# Power_RPI_conn.net
KiCad netlist of a schematic drawn in Altium Designer
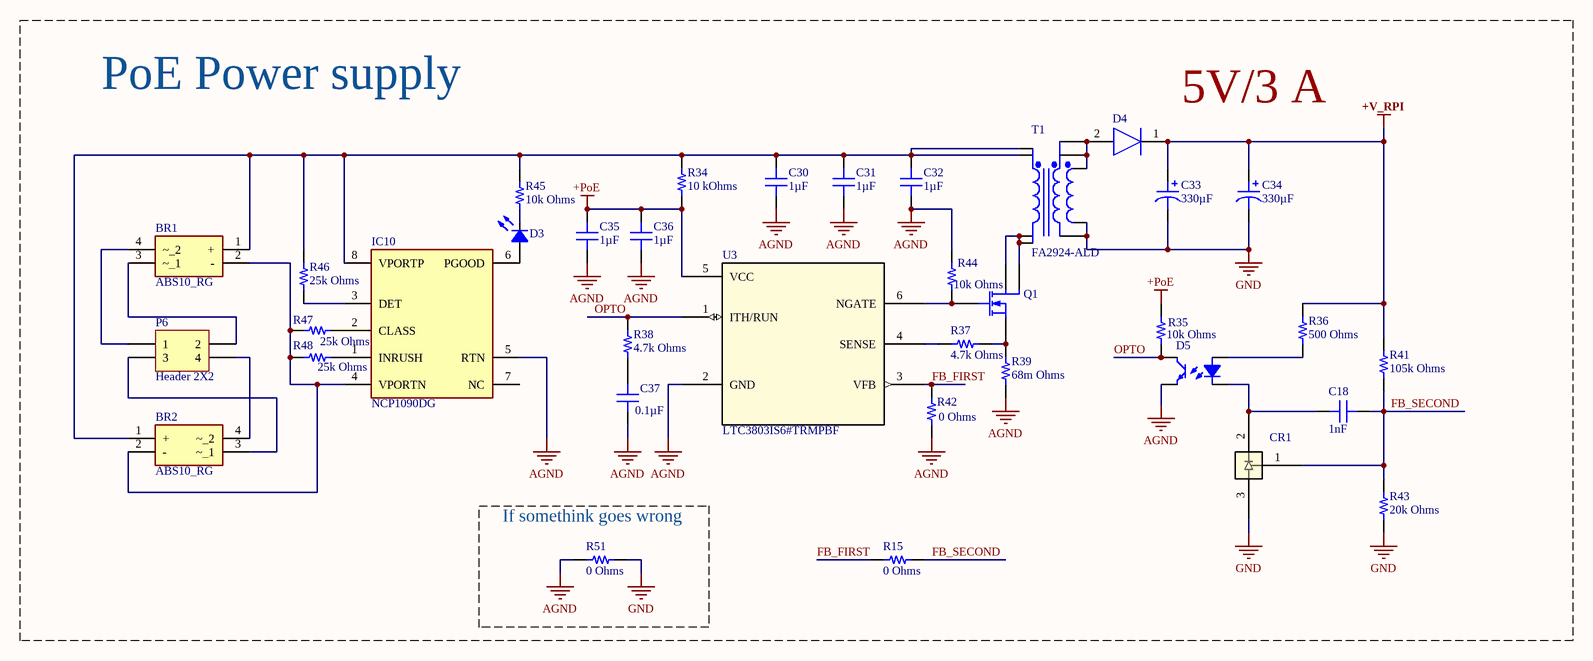
[diagram p0: Power+RPI_conn.SchDoc]

(export (version "E")
  (design (tool "Eeschema 10.0.6"))
  (components
    (comp (ref "BR1")
      (value "ABS10_RG")
      (footprint "SamacSys:SOP400P645X160-4N")
      (description "Bridge Rectifier")
      (fields (field (name "MANUFACTURER_PART_NUMBER") "ABS10 RG"))
      (libsource (lib "*") (part "ABS10_RG"))
    )
    (comp (ref "BR2")
      (value "ABS10_RG")
      (footprint "SamacSys:SOP400P645X160-4N")
      (description "Bridge Rectifier")
      (fields (field (name "MANUFACTURER_PART_NUMBER") "ABS10 RG"))
      (libsource (lib "") (part "ABS10_RG_1"))
    )
    (comp (ref "C18")
      (value "1nF")
      (footprint "CAP 0603_1608")
      (description "CAP CER 0.1UF 10V X7R 0603")
      (fields (field (name "PART NUMBER") "100X14W104MV4T"))
      (libsource (lib "Celestial Altium Library - altium_library") (part "Capacitor"))
    )
    (comp (ref "C30")
      (value "1µF")
      (footprint "CAP 1206_3216 - 1.8MM")
      (description "CAP CER 1UF 100V X7R 1206")
      (fields (field (name "PART NUMBER") "C1206C105M1RACTU") (field (name "MANUFACTURER") "KEMET"))
      (libsource (lib "Celestial Altium Library - altium_library") (part "Capacitor"))
    )
    (comp (ref "C31")
      (value "1µF")
      (footprint "CAP 1206_3216 - 1.8MM")
      (description "CAP CER 1UF 100V X7R 1206")
      (fields (field (name "PART NUMBER") "C1206C105M1RACTU") (field (name "MANUFACTURER") "KEMET"))
      (libsource (lib "Celestial Altium Library - altium_library") (part "Capacitor"))
    )
    (comp (ref "C32")
      (value "1µF")
      (footprint "CAP 1206_3216 - 1.8MM")
      (description "CAP CER 1UF 100V X7R 1206")
      (fields (field (name "PART NUMBER") "C1206C105M1RACTU") (field (name "MANUFACTURER") "KEMET"))
      (libsource (lib "Celestial Altium Library - altium_library") (part "Capacitor"))
    )
    (comp (ref "C33")
      (value "330µF")
      (footprint "CAP POL 2917_7343")
      (description "CAP TANT 330UF 20% 10V 2917")
      (fields (field (name "PART NUMBER") "TPSE337M010R0060") (field (name "MANUFACTURER") "AVX Corporation"))
      (libsource (lib "Celestial Altium Library - altium_library") (part "Polarised Capacitor"))
    )
    (comp (ref "C34")
      (value "330µF")
      (footprint "CAP POL 2917_7343")
      (description "CAP TANT 330UF 20% 10V 2917")
      (fields (field (name "PART NUMBER") "TPSE337M010R0060") (field (name "MANUFACTURER") "AVX Corporation"))
      (libsource (lib "Celestial Altium Library - altium_library") (part "Polarised Capacitor"))
    )
    (comp (ref "C35")
      (value "1µF")
      (footprint "CAP 1206_3216 - 1.8MM")
      (description "CAP CER 1UF 100V X7R 1206")
      (fields (field (name "PART NUMBER") "C1206C105M1RACTU") (field (name "MANUFACTURER") "KEMET"))
      (libsource (lib "Celestial Altium Library - altium_library") (part "Capacitor"))
    )
    (comp (ref "C36")
      (value "1µF")
      (footprint "CAP 1206_3216 - 1.8MM")
      (description "CAP CER 1UF 100V X7R 1206")
      (fields (field (name "PART NUMBER") "C1206C105M1RACTU") (field (name "MANUFACTURER") "KEMET"))
      (libsource (lib "Celestial Altium Library - altium_library") (part "Capacitor"))
    )
    (comp (ref "C37")
      (value "0.1µF")
      (footprint "CAP 0603_1608")
      (description "CAP CER 0.1UF 10V X7R 0603")
      (fields (field (name "PART NUMBER") "100X14W104MV4T"))
      (libsource (lib "Celestial Altium Library - altium_library") (part "Capacitor"))
    )
    (comp (ref "CR1")
      (value "TLV431BFTA")
      (footprint "SOT23_DIO")
      (description "No Description Available")
      (fields (field (name "COPYRIGHT") "Copyright (C) 2018 Accelerated Designs. All rights reserved"))
      (libsource (lib "tlv431") (part "TLV431BFTA"))
    )
    (comp (ref "D3")
      (value "~")
      (footprint "LED 0603_1608 RED")
      (description "LED RED 0603 SMD")
      (fields (field (name "PART NUMBER") "5973005507F"))
      (libsource (lib "Celestial Altium Library - altium_library") (part "LED"))
    )
    (comp (ref "D4")
      (value "SK56B_R4")
      (footprint "SamacSys:DIONM5236X261N")
      (description "Diode")
      (fields
        (field (name "MANUFACTURER_PART_NUMBER") "SK56B R4")
        (field (name "MOUSER PART NUMBER") "821-SK56BR4")
      )
      (libsource (lib "*") (part "SK56B_R4"))
    )
    (comp (ref "D5")
      (value "LTV-817S-TA1")
      (footprint "LITEON LTV-817")
      (description "OPTOISOLATR 5KV TRANSISTOR 4-SMD")
      (fields (field (name "MANUFACTURER") "Lite-On Inc."))
      (libsource (lib "Celestial Altium Library - altium_library") (part "Optoisolator"))
    )
    (comp (ref "IC10")
      (value "NCP1090DG")
      (footprint "SamacSys:SOIC127P600X175-8N")
      (description "Integrated Circuit")
      (fields (field (name "MOUSER PART NUMBER") "863-NCP1090DG"))
      (libsource (lib "SamacSys") (part "NCP1090DG"))
    )
    (comp (ref "P6")
      (value "Header 2X2")
      (footprint "HDR2X2")
      (description "Header, 2-Pin, Dual row")
      (fields (field (name "PUBLISHER") "Altium Limited"))
      (libsource (lib "Miscellaneous Connectors") (part "Header 2X2"))
    )
    (comp (ref "Q1")
      (value "IRFL4315TRPBF")
      (footprint "SOT230P700X180-4N")
      (description "MOSFET (N-Channel)")
      (fields (field (name "MOUSER PART NUMBER") "942-IRFL4315TRPBF"))
      (libsource (lib "SamacSys") (part "IRFL4315TRPBF"))
    )
    (comp (ref "R15")
      (value "0 Ohms")
      (footprint "RES 2512_6432")
      (description "RES 0 OHM JUMPER 1W 2512")
      (fields
        (field (name "PART NUMBER") "RMCF2512ZT0R00")
        (field (name "MANUFACTURER") "Stackpole Electronics Inc")
      )
      (libsource (lib "Celestial Altium Library - altium_library") (part "Resistor"))
    )
    (comp (ref "R34")
      (value "10 kOhms")
      (footprint "RES 1206_3216")
      (description "RES SMD 33K OHM 0.1% 1/4W 1206")
      (fields (field (name "PART NUMBER") "RT1206BRD0733KL") (field (name "MANUFACTURER") "Yageo"))
      (libsource (lib "Celestial Altium Library - altium_library") (part "Resistor"))
    )
    (comp (ref "R35")
      (value "10k Ohms")
      (footprint "RES 0603_1608")
      (description "RES 100 OHM 0.1% 1/16W 0603")
      (fields (field (name "PART NUMBER") "RNCS0603BKE100R"))
      (libsource (lib "Celestial Altium Library - altium_library") (part "Resistor"))
    )
    (comp (ref "R36")
      (value "500 Ohms")
      (footprint "RES 0603_1608")
      (description "RES 100 OHM 0.1% 1/16W 0603")
      (fields (field (name "PART NUMBER") "RNCS0603BKE100R"))
      (libsource (lib "Celestial Altium Library - altium_library") (part "Resistor"))
    )
    (comp (ref "R37")
      (value "4.7k Ohms")
      (footprint "RES 0603_1608")
      (description "RES 100 OHM 0.1% 1/16W 0603")
      (fields (field (name "PART NUMBER") "RNCS0603BKE100R"))
      (libsource (lib "Celestial Altium Library - altium_library") (part "Resistor"))
    )
    (comp (ref "R38")
      (value "4.7k Ohms")
      (footprint "RES 0603_1608")
      (description "RES 100 OHM 0.1% 1/16W 0603")
      (fields (field (name "PART NUMBER") "RNCS0603BKE100R"))
      (libsource (lib "Celestial Altium Library - altium_library") (part "Resistor"))
    )
    (comp (ref "R39")
      (value "68m Ohms")
      (footprint "RES 1206_3216")
      (description "1206 SIZE, 0.25W, 350 OHM, 0.01%")
      (fields (field (name "PART NUMBER") "URG3216L-3500-L-T05") (field (name "MANUFACTURER") "Susumu"))
      (libsource (lib "Celestial Altium Library - altium_library") (part "Resistor"))
    )
    (comp (ref "R41")
      (value "105k Ohms")
      (footprint "RES 0603_1608")
      (description "RES 100 OHM 0.1% 1/16W 0603")
      (fields (field (name "PART NUMBER") "RNCS0603BKE100R"))
      (libsource (lib "Celestial Altium Library - altium_library") (part "Resistor"))
    )
    (comp (ref "R42")
      (value "0 Ohms")
      (footprint "RES 0603_1608")
      (description "RES 100 OHM 0.1% 1/16W 0603")
      (fields (field (name "PART NUMBER") "RNCS0603BKE100R"))
      (libsource (lib "Celestial Altium Library - altium_library") (part "Resistor"))
    )
    (comp (ref "R43")
      (value "20k Ohms")
      (footprint "RES 0603_1608")
      (description "RES 100 OHM 0.1% 1/16W 0603")
      (fields (field (name "PART NUMBER") "RNCS0603BKE100R"))
      (libsource (lib "Celestial Altium Library - altium_library") (part "Resistor"))
    )
    (comp (ref "R44")
      (value "10k Ohms")
      (footprint "RES 0603_1608")
      (description "RES 100 OHM 0.1% 1/16W 0603")
      (fields (field (name "PART NUMBER") "RNCS0603BKE100R"))
      (libsource (lib "Celestial Altium Library - altium_library") (part "Resistor"))
    )
    (comp (ref "R45")
      (value "10k Ohms")
      (footprint "RES 0603_1608")
      (description "RES 100 OHM 0.1% 1/16W 0603")
      (fields (field (name "PART NUMBER") "RNCS0603BKE100R"))
      (libsource (lib "Celestial Altium Library - altium_library") (part "Resistor"))
    )
    (comp (ref "R46")
      (value "25k Ohms")
      (footprint "RES 0603_1608")
      (description "RES 100 OHM 0.1% 1/16W 0603")
      (fields (field (name "PART NUMBER") "RNCS0603BKE100R"))
      (libsource (lib "Celestial Altium Library - altium_library") (part "Resistor"))
    )
    (comp (ref "R47")
      (value "25k Ohms")
      (footprint "RES 0603_1608")
      (description "RES 100 OHM 0.1% 1/16W 0603")
      (fields (field (name "PART NUMBER") "RNCS0603BKE100R"))
      (libsource (lib "Celestial Altium Library - altium_library") (part "Resistor"))
    )
    (comp (ref "R48")
      (value "25k Ohms")
      (footprint "RES 0603_1608")
      (description "RES 100 OHM 0.1% 1/16W 0603")
      (fields (field (name "PART NUMBER") "RNCS0603BKE100R"))
      (libsource (lib "Celestial Altium Library - altium_library") (part "Resistor"))
    )
    (comp (ref "R51")
      (value "0 Ohms")
      (footprint "RES 2512_6432")
      (description "RES 0 OHM JUMPER 1W 2512")
      (fields
        (field (name "PART NUMBER") "RMCF2512ZT0R00")
        (field (name "MANUFACTURER") "Stackpole Electronics Inc")
      )
      (libsource (lib "Celestial Altium Library - altium_library") (part "Resistor"))
    )
    (comp (ref "T1")
      (value "FA2924-ALD")
      (footprint "SamacSys2:FA2924ALD")
      (description "Transformer")
      (fields (field (name "MOUSER PART NUMBER") "994-FA2924-ALD"))
      (libsource (lib "RPI_POE_ADC_SHIELD") (part "FA2924-ALD"))
    )
    (comp (ref "U3")
      (value "LTC3803IS6#TRMPBF")
      (footprint "SamacSys:SOT95P280X100-6N")
      (description "No Description Available")
      (fields
        (field (name "MANUFACTURER_PART_NUMBER") "LTC3803IS6-5#TRMPBF")
        (field (name "COPYRIGHT") "Copyright (C) 2018 Accelerated Designs. All rights reserved")
      )
      (libsource (lib "LTC3803") (part "LTC3803IS6-5#TRMPBF"))
    )
  )
  (nets
    (net (code "1") (name "+PoE") (class "Default")
      (node (ref "C35") (pin "2") (pinfunction "2_2") (pintype "passive"))
      (node (ref "C36") (pin "2") (pinfunction "2_2") (pintype "passive"))
      (node (ref "R34") (pin "1") (pinfunction "1_1") (pintype "passive"))
      (node (ref "R35") (pin "2") (pinfunction "2_2") (pintype "passive"))
      (node (ref "U3") (pin "5") (pinfunction "VCC_5") (pintype "power_in"))
    )
    (net (code "2") (name "+V_RPI") (class "Default")
      (node (ref "C33") (pin "1") (pinfunction "1_1") (pintype "passive"))
      (node (ref "C34") (pin "1") (pinfunction "1_1") (pintype "passive"))
      (node (ref "D4") (pin "1") (pinfunction "K_1") (pintype "passive"))
      (node (ref "R36") (pin "2") (pinfunction "2_2") (pintype "passive"))
      (node (ref "R41") (pin "1") (pinfunction "1_1") (pintype "passive"))
    )
    (net (code "3") (name "/FB_FIRST") (class "Default")
      (node (ref "R15") (pin "1") (pinfunction "1_1") (pintype "passive"))
      (node (ref "R42") (pin "1") (pinfunction "1_1") (pintype "passive"))
      (node (ref "U3") (pin "3") (pinfunction "VFB_3") (pintype "output"))
    )
    (net (code "4") (name "/FB_SECOND") (class "Default")
      (node (ref "C18") (pin "1") (pinfunction "1_1") (pintype "passive"))
      (node (ref "CR1") (pin "1") (pinfunction "1_1") (pintype "passive"))
      (node (ref "R15") (pin "2") (pinfunction "2_2") (pintype "passive"))
      (node (ref "R41") (pin "2") (pinfunction "2_2") (pintype "passive"))
      (node (ref "R43") (pin "1") (pinfunction "1_1") (pintype "passive"))
    )
    (net (code "5") (name "/OPTO") (class "Default")
      (node (ref "D5") (pin "4") (pinfunction "4_4") (pintype "passive"))
      (node (ref "R35") (pin "1") (pinfunction "1_1") (pintype "passive"))
      (node (ref "R38") (pin "1") (pinfunction "1_1") (pintype "passive"))
      (node (ref "U3") (pin "1") (pinfunction "ITH/RUN_1") (pintype "bidirectional"))
    )
    (net (code "6") (name "AGND") (class "Default")
      (node (ref "C30") (pin "1") (pinfunction "1_1") (pintype "passive"))
      (node (ref "C31") (pin "1") (pinfunction "1_1") (pintype "passive"))
      (node (ref "C32") (pin "1") (pinfunction "1_1") (pintype "passive"))
      (node (ref "C35") (pin "1") (pinfunction "1_1") (pintype "passive"))
      (node (ref "C36") (pin "1") (pinfunction "1_1") (pintype "passive"))
      (node (ref "C37") (pin "1") (pinfunction "1_1") (pintype "passive"))
      (node (ref "D5") (pin "3") (pinfunction "3_3") (pintype "passive"))
      (node (ref "IC10") (pin "5") (pinfunction "RTN_5") (pintype "passive"))
      (node (ref "R39") (pin "1") (pinfunction "1_1") (pintype "passive"))
      (node (ref "R42") (pin "2") (pinfunction "2_2") (pintype "passive"))
      (node (ref "R44") (pin "2") (pinfunction "2_2") (pintype "passive"))
      (node (ref "R51") (pin "1") (pinfunction "1_1") (pintype "passive"))
      (node (ref "U3") (pin "2") (pinfunction "GND_2") (pintype "power_in"))
    )
    (net (code "7") (name "GND") (class "Default")
      (node (ref "C33") (pin "2") (pinfunction "2_2") (pintype "passive"))
      (node (ref "C34") (pin "2") (pinfunction "2_2") (pintype "passive"))
      (node (ref "CR1") (pin "3") (pinfunction "3_3") (pintype "passive"))
      (node (ref "R43") (pin "2") (pinfunction "2_2") (pintype "passive"))
      (node (ref "R51") (pin "2") (pinfunction "2_2") (pintype "passive"))
      (node (ref "T1") (pin "10") (pinfunction "Sec-_10") (pintype "passive"))
      (node (ref "T1") (pin "9") (pinfunction "Sec-_9") (pintype "passive"))
    )
    (net (code "8") (name "Net-(BR1-+)") (class "Default")
      (node (ref "BR1") (pin "1") (pinfunction "+_1") (pintype "passive"))
      (node (ref "BR2") (pin "1") (pinfunction "+_1") (pintype "passive"))
      (node (ref "C30") (pin "2") (pinfunction "2_2") (pintype "passive"))
      (node (ref "C31") (pin "2") (pinfunction "2_2") (pintype "passive"))
      (node (ref "C32") (pin "2") (pinfunction "2_2") (pintype "passive"))
      (node (ref "IC10") (pin "8") (pinfunction "VPORTP_8") (pintype "passive"))
      (node (ref "R34") (pin "2") (pinfunction "2_2") (pintype "passive"))
      (node (ref "R45") (pin "1") (pinfunction "1_1") (pintype "passive"))
      (node (ref "R46") (pin "1") (pinfunction "1_1") (pintype "passive"))
      (node (ref "T1") (pin "1") (pinfunction "Pri+_1") (pintype "passive"))
      (node (ref "T1") (pin "5") (pinfunction "Pri+_5") (pintype "passive"))
    )
    (net (code "9") (name "Net-(BR1--)") (class "Default")
      (node (ref "BR1") (pin "2") (pinfunction "-_2") (pintype "passive"))
      (node (ref "BR2") (pin "2") (pinfunction "-_2") (pintype "passive"))
      (node (ref "IC10") (pin "4") (pinfunction "VPORTN_4") (pintype "passive"))
      (node (ref "R47") (pin "1") (pinfunction "1_1") (pintype "passive"))
      (node (ref "R48") (pin "1") (pinfunction "1_1") (pintype "passive"))
    )
    (net (code "10") (name "Net-(BR1-~_1)") (class "Default")
      (node (ref "BR1") (pin "3") (pinfunction "~_1_3") (pintype "passive"))
      (node (ref "P6") (pin "2") (pinfunction "2_2") (pintype "passive"))
    )
    (net (code "11") (name "Net-(BR1-~_2)") (class "Default")
      (node (ref "BR1") (pin "4") (pinfunction "~_2_4") (pintype "passive"))
      (node (ref "P6") (pin "1") (pinfunction "1_1") (pintype "passive"))
    )
    (net (code "12") (name "Net-(BR2-~_1)") (class "Default")
      (node (ref "BR2") (pin "3") (pinfunction "~_1_3") (pintype "passive"))
      (node (ref "P6") (pin "3") (pinfunction "3_3") (pintype "passive"))
    )
    (net (code "13") (name "Net-(BR2-~_2)") (class "Default")
      (node (ref "BR2") (pin "4") (pinfunction "~_2_4") (pintype "passive"))
      (node (ref "P6") (pin "4") (pinfunction "4_4") (pintype "passive"))
    )
    (net (code "14") (name "Net-(C18-Pad2)") (class "Default")
      (node (ref "C18") (pin "2") (pinfunction "2_2") (pintype "passive"))
      (node (ref "CR1") (pin "2") (pinfunction "2_2") (pintype "passive"))
      (node (ref "D5") (pin "2") (pinfunction "2_2") (pintype "passive"))
    )
    (net (code "15") (name "Net-(C37-Pad2)") (class "Default")
      (node (ref "C37") (pin "2") (pinfunction "2_2") (pintype "passive"))
      (node (ref "R38") (pin "2") (pinfunction "2_2") (pintype "passive"))
    )
    (net (code "16") (name "Net-(D3-Pad2)") (class "Default")
      (node (ref "D3") (pin "2") (pinfunction "2_2") (pintype "passive"))
      (node (ref "R45") (pin "2") (pinfunction "2_2") (pintype "passive"))
    )
    (net (code "17") (name "Net-(D4-A)") (class "Default")
      (node (ref "D4") (pin "2") (pinfunction "A_2") (pintype "passive"))
      (node (ref "T1") (pin "6") (pinfunction "Sec+_6") (pintype "passive"))
      (node (ref "T1") (pin "7") (pinfunction "Sec+_7") (pintype "passive"))
      (node (ref "T1") (pin "8") (pinfunction "Sec+_8") (pintype "passive"))
    )
    (net (code "18") (name "Net-(D5-Pad1)") (class "Default")
      (node (ref "D5") (pin "1") (pinfunction "1_1") (pintype "passive"))
      (node (ref "R36") (pin "1") (pinfunction "1_1") (pintype "passive"))
    )
    (net (code "19") (name "Net-(IC10-CLASS)") (class "Default")
      (node (ref "IC10") (pin "2") (pinfunction "CLASS_2") (pintype "passive"))
      (node (ref "R47") (pin "2") (pinfunction "2_2") (pintype "passive"))
    )
    (net (code "20") (name "Net-(IC10-DET)") (class "Default")
      (node (ref "IC10") (pin "3") (pinfunction "DET_3") (pintype "passive"))
      (node (ref "R46") (pin "2") (pinfunction "2_2") (pintype "passive"))
    )
    (net (code "21") (name "Net-(IC10-INRUSH)") (class "Default")
      (node (ref "IC10") (pin "1") (pinfunction "INRUSH_1") (pintype "passive"))
      (node (ref "R48") (pin "2") (pinfunction "2_2") (pintype "passive"))
    )
    (net (code "22") (name "Net-(IC10-PGOOD)") (class "Default")
      (node (ref "D3") (pin "1") (pinfunction "1_1") (pintype "passive"))
      (node (ref "IC10") (pin "6") (pinfunction "PGOOD_6") (pintype "passive"))
    )
    (net (code "23") (name "Net-(Q1-D)") (class "Default")
      (node (ref "Q1") (pin "2") (pinfunction "D_2") (pintype "passive"))
      (node (ref "Q1") (pin "4") (pinfunction "D_2_4") (pintype "passive"))
      (node (ref "T1") (pin "2") (pinfunction "Pri-_2") (pintype "passive"))
      (node (ref "T1") (pin "3") (pinfunction "Pri-_3") (pintype "passive"))
    )
    (net (code "24") (name "Net-(Q1-G)") (class "Default")
      (node (ref "Q1") (pin "1") (pinfunction "G_1") (pintype "passive"))
      (node (ref "R44") (pin "1") (pinfunction "1_1") (pintype "passive"))
      (node (ref "U3") (pin "6") (pinfunction "NGATE_6") (pintype "passive"))
    )
    (net (code "25") (name "Net-(Q1-S)") (class "Default")
      (node (ref "Q1") (pin "3") (pinfunction "S_3") (pintype "passive"))
      (node (ref "R37") (pin "1") (pinfunction "1_1") (pintype "passive"))
      (node (ref "R39") (pin "2") (pinfunction "2_2") (pintype "passive"))
    )
    (net (code "26") (name "Net-(U3-SENSE)") (class "Default")
      (node (ref "R37") (pin "2") (pinfunction "2_2") (pintype "passive"))
      (node (ref "U3") (pin "4") (pinfunction "SENSE_4") (pintype "passive"))
    )
    (net (code "27") (name "unconnected-(IC10-NC-Pad7)") (class "Default")
      (node (ref "IC10") (pin "7") (pinfunction "NC_7") (pintype "passive"))
    )
  )
)
